# Stm32Printer.net
KiCad netlist of a schematic drawn in EasyEDA Pro
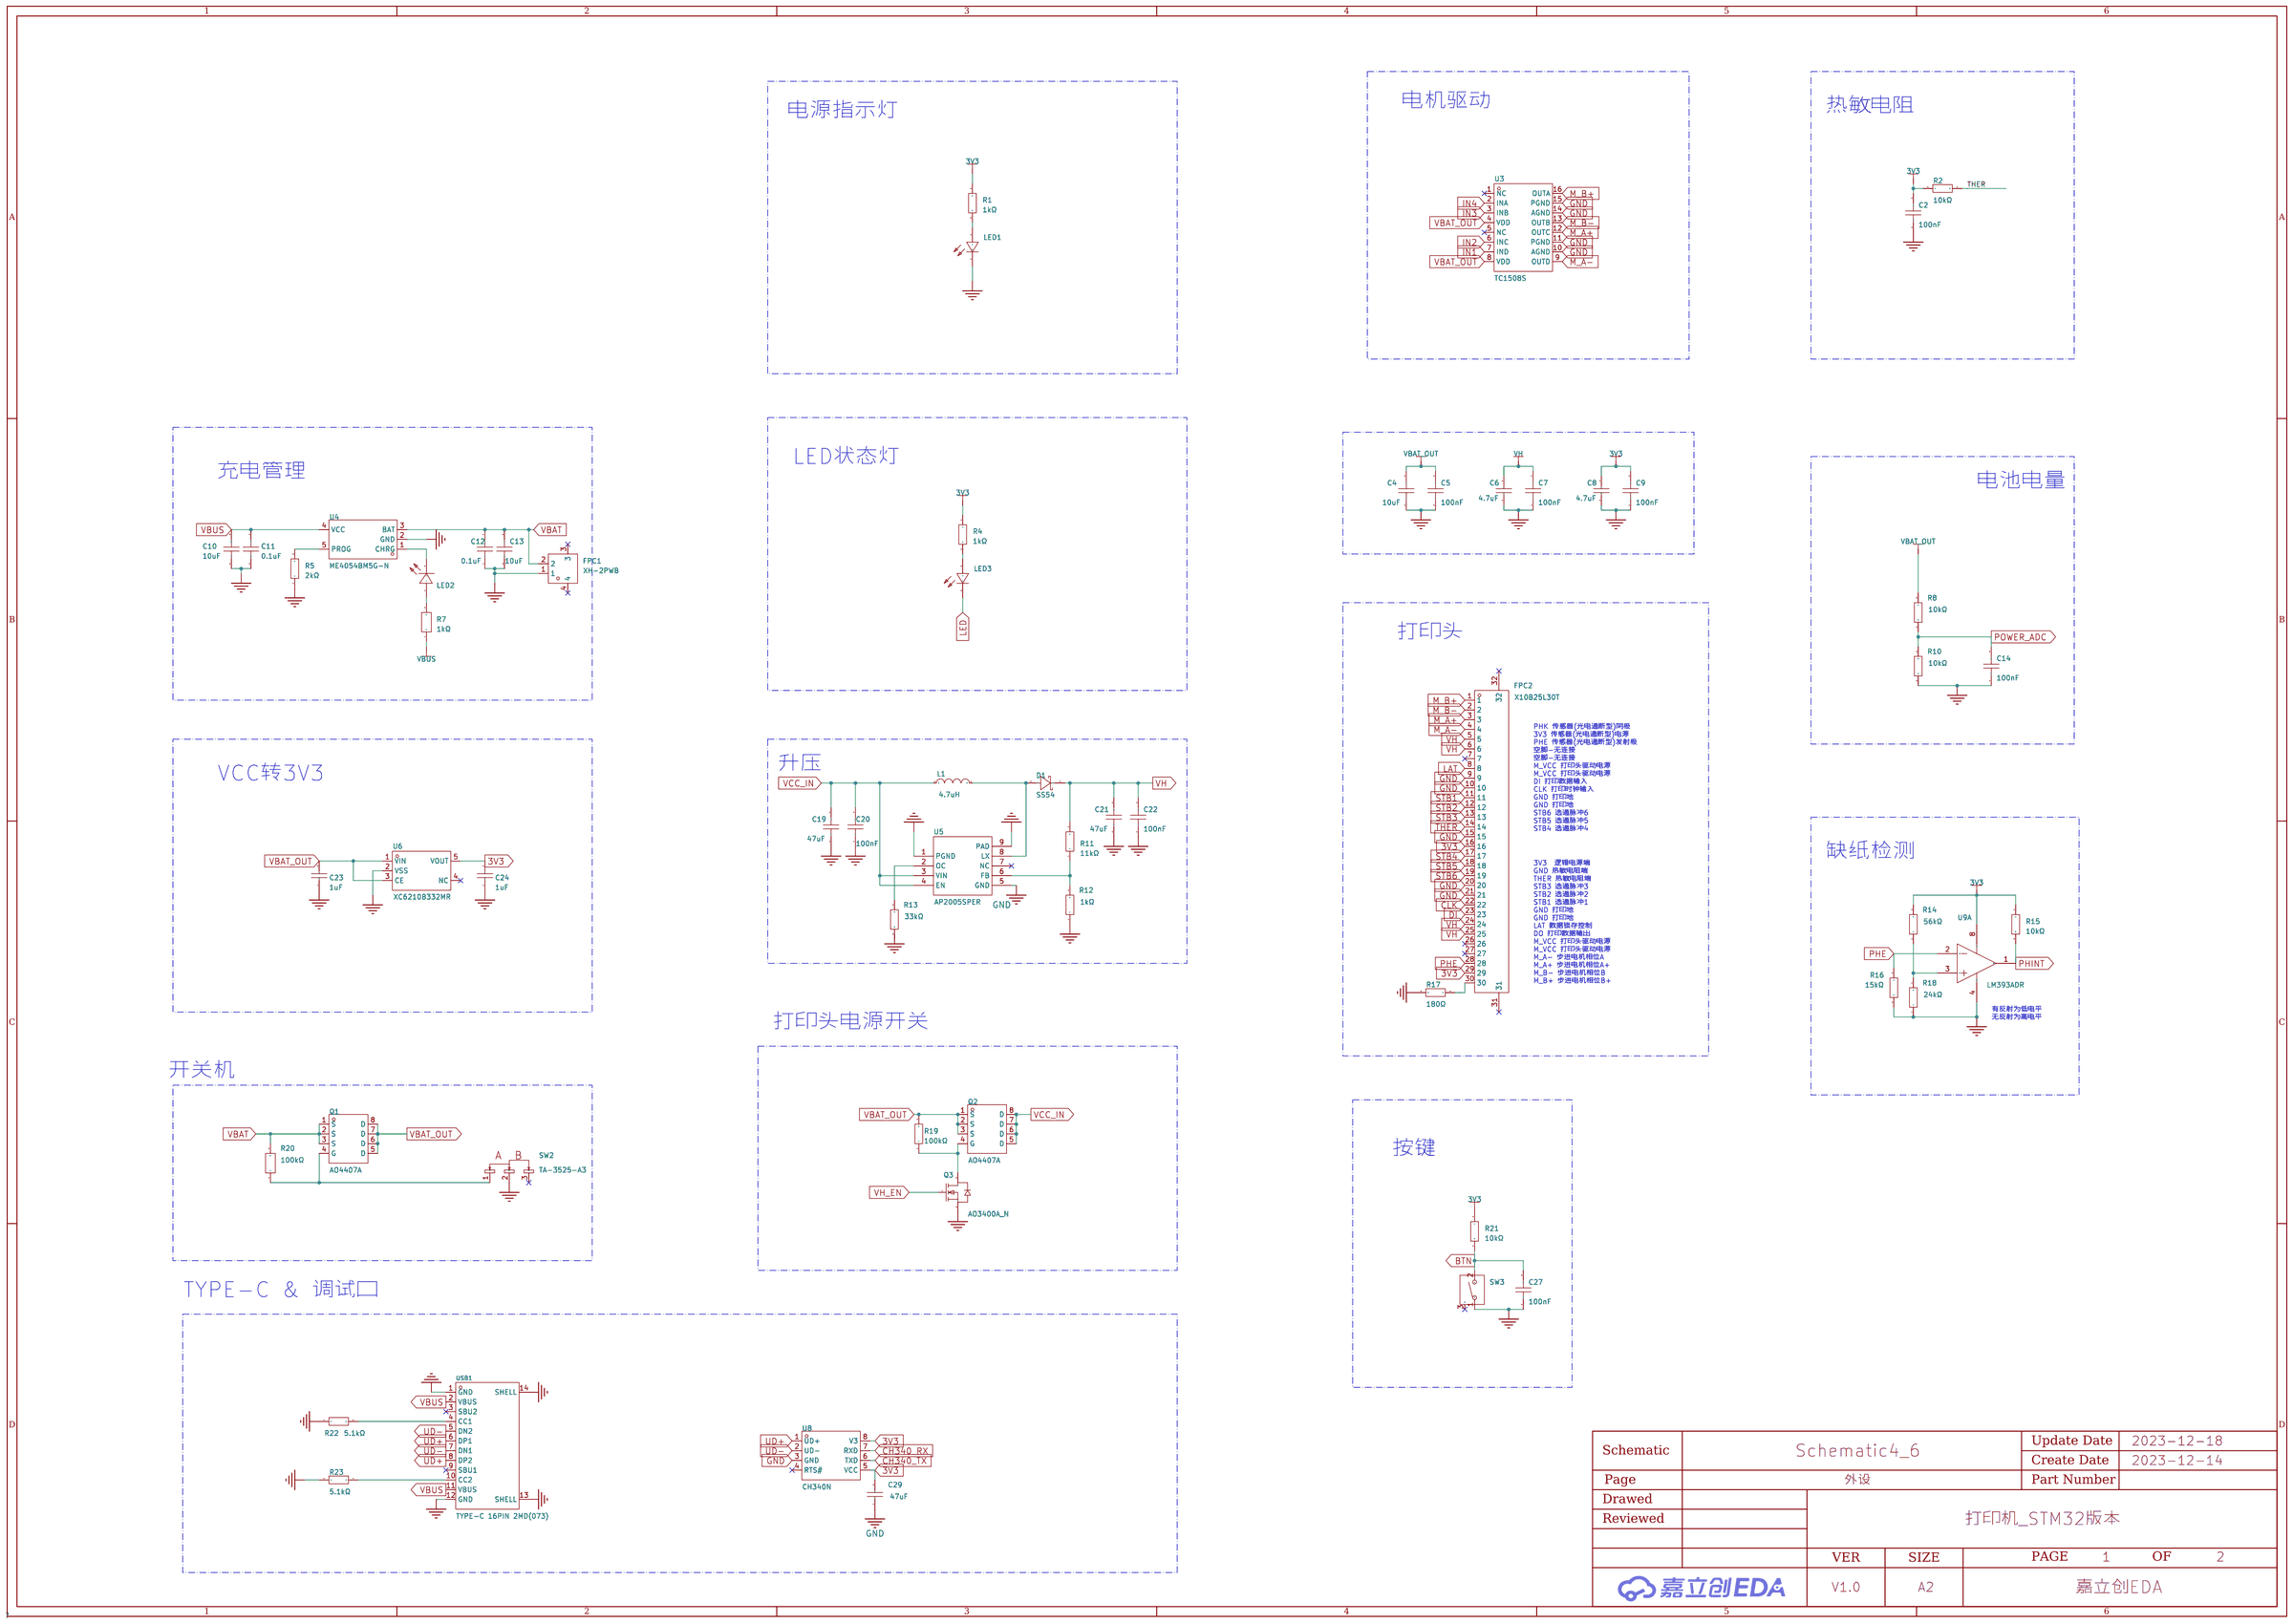
[diagram p0: 外设]
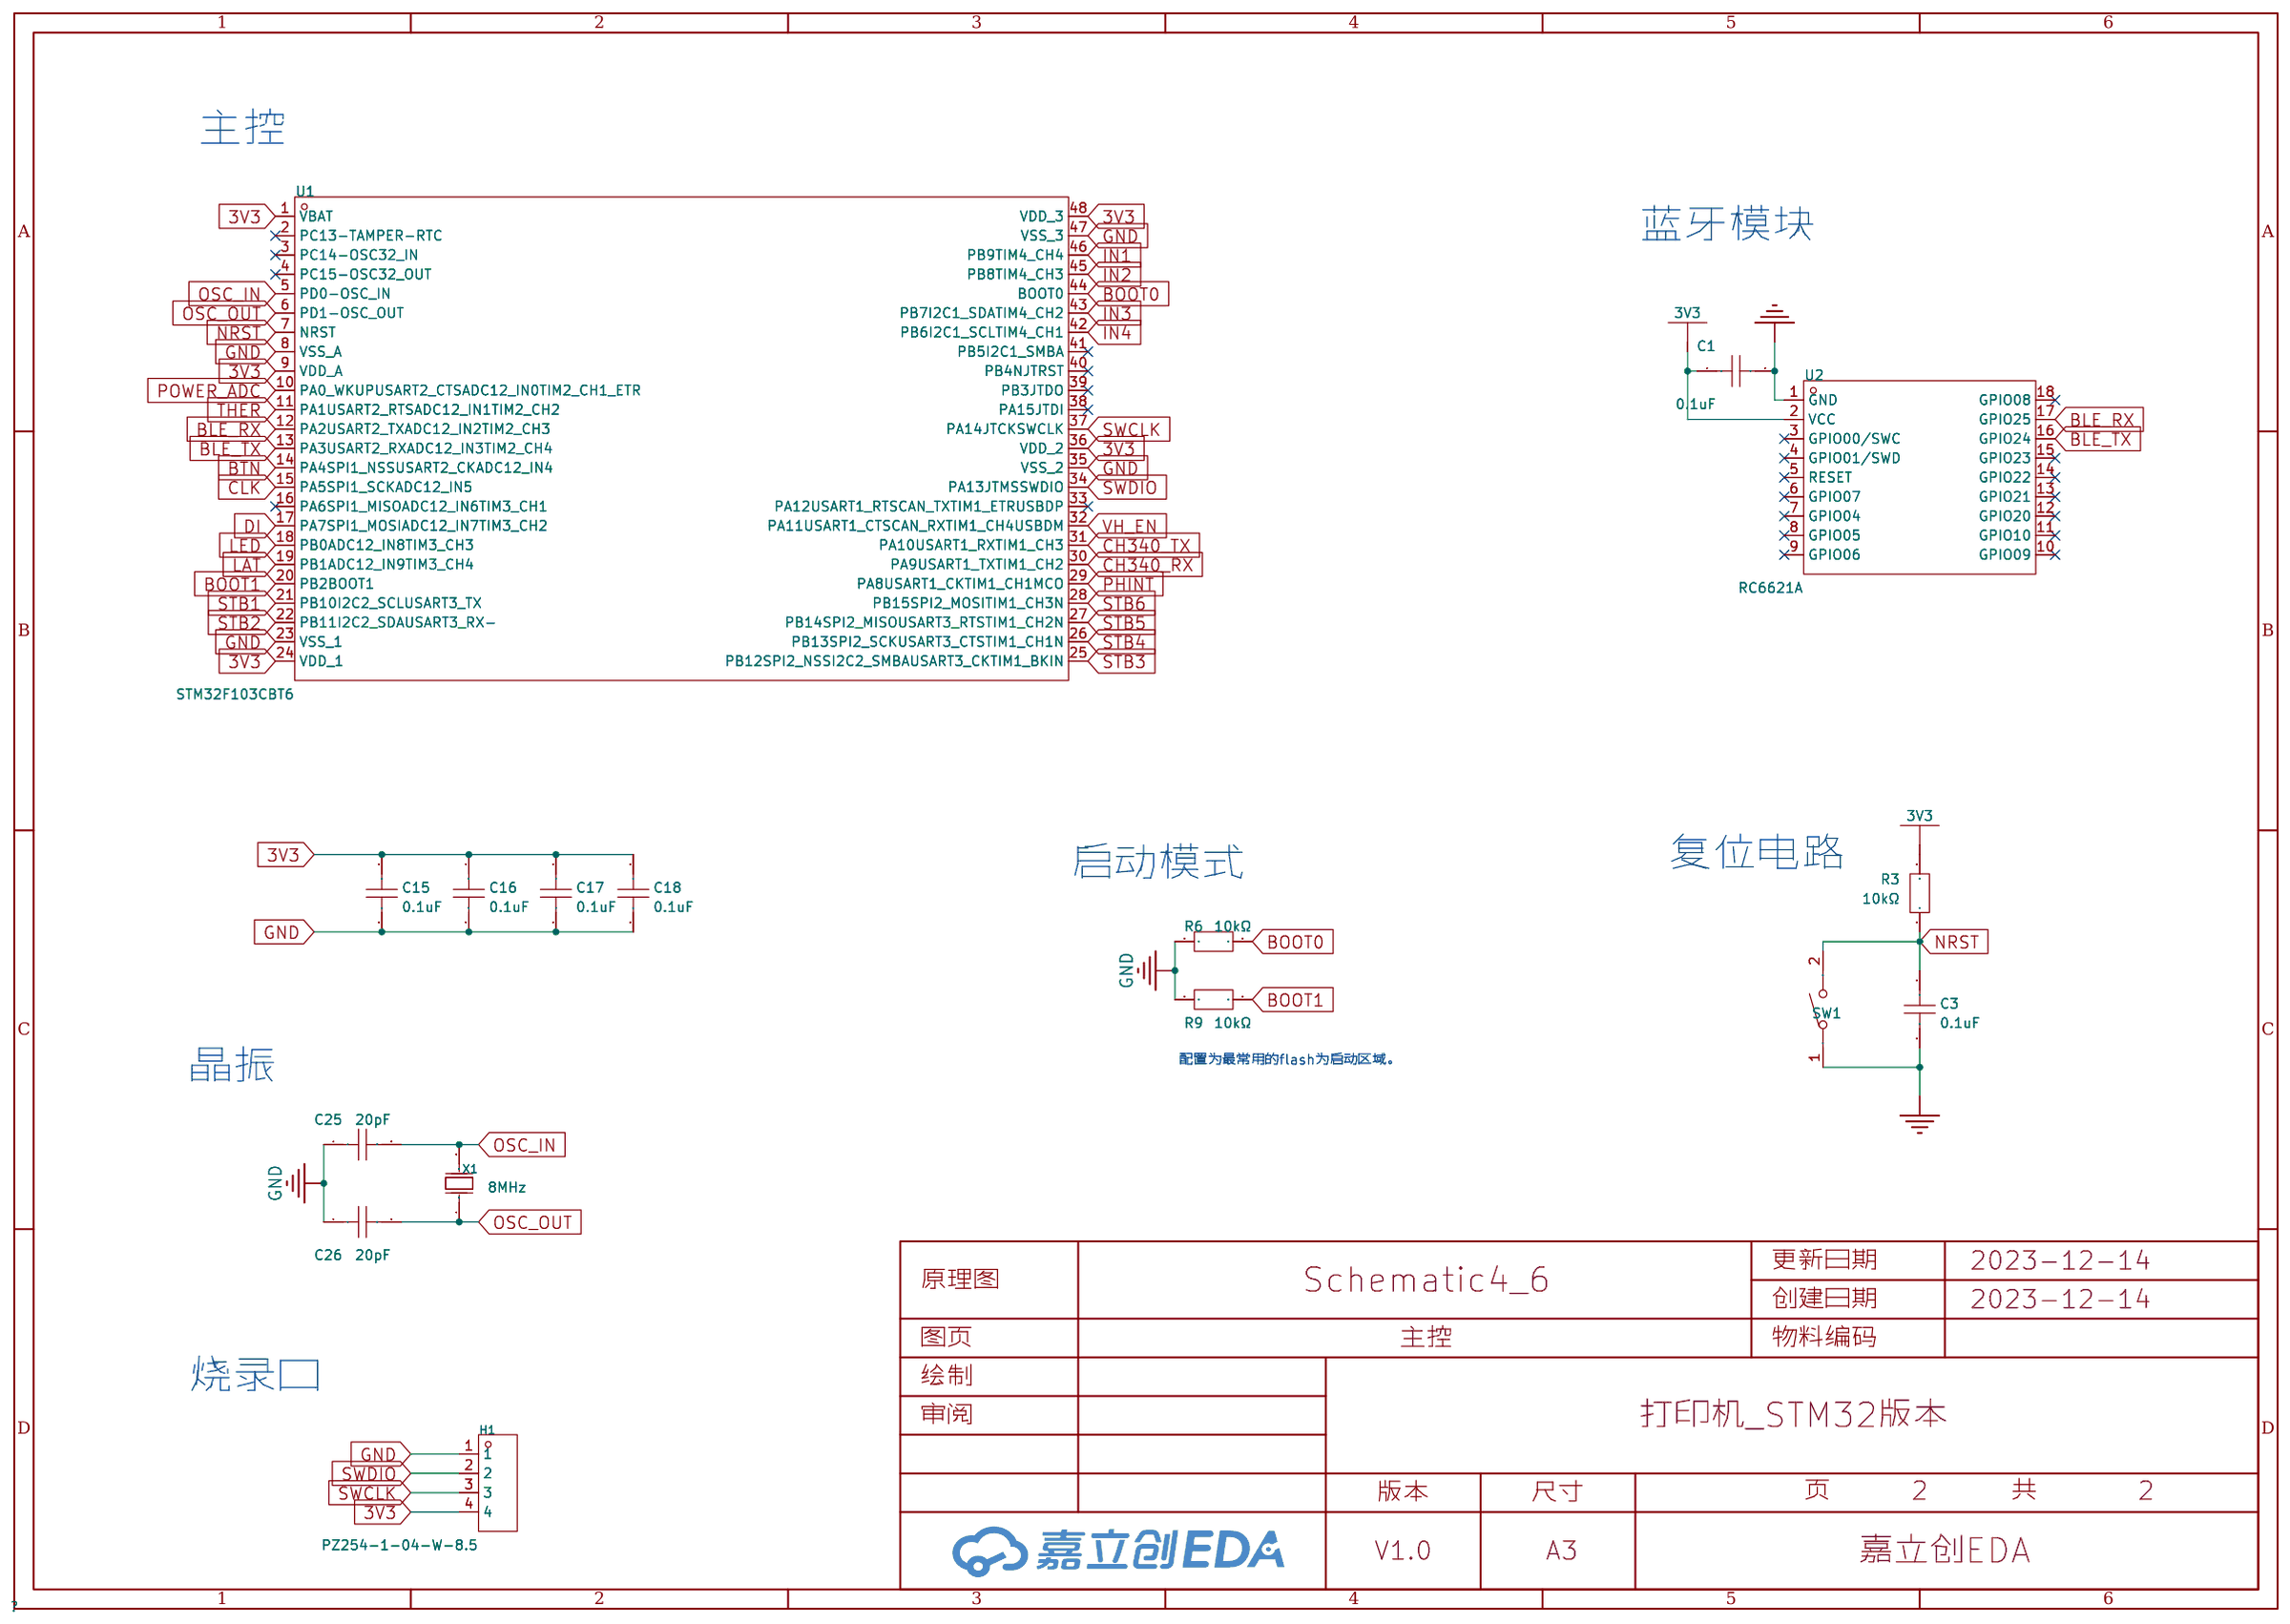
[diagram p1: 主控]

(export (version "E")
  (design (tool "Eeschema 10.0.6"))
  (components
    (comp (ref "C2")
      (value "100nF")
      (footprint "easyedapro:C0603")
      (description "容值:100nF;精度:±10%;额定电压:50V;材质(温度系数):X7R;")
      (fields
        (field (name "Manufacturer Part") "CL10B104KB8NNNC")
        (field (name "Manufacturer") "SAMSUNG(三星)")
      )
      (libsource (lib "easyedapro") (part "CL10B104KB8NNNC"))
    )
    (comp (ref "C4")
      (value "10uF")
      (footprint "easyedapro:C0603")
      (description "容值:10uF;精度:±20%;额定电压:25V;材质(温度系数):X5R;")
      (fields
        (field (name "Manufacturer Part") "CL10A106MA8NRNC")
        (field (name "Manufacturer") "SAMSUNG(三星)")
      )
      (libsource (lib "easyedapro") (part "CL10A106MA8NRNC"))
    )
    (comp (ref "C5")
      (value "100nF")
      (footprint "easyedapro:C0603")
      (description "容值:100nF;精度:±10%;额定电压:50V;材质(温度系数):X7R;")
      (fields
        (field (name "Manufacturer Part") "CL10B104KB8NNNC")
        (field (name "Manufacturer") "SAMSUNG(三星)")
      )
      (libsource (lib "easyedapro") (part "CL10B104KB8NNNC"))
    )
    (comp (ref "C6")
      (value "4.7uF")
      (footprint "easyedapro:C0603")
      (description "容值:4.7uF;精度:±10%;额定电压:25V;材质(温度系数):X5R;")
      (fields
        (field (name "Manufacturer Part") "CL10A475KA8NQNC")
        (field (name "Manufacturer") "SAMSUNG(三星)")
      )
      (libsource (lib "easyedapro") (part "CL10A475KA8NQNC"))
    )
    (comp (ref "C7")
      (value "100nF")
      (footprint "easyedapro:C0603")
      (description "容值:100nF;精度:±10%;额定电压:50V;材质(温度系数):X7R;")
      (fields
        (field (name "Manufacturer Part") "CL10B104KB8NNNC")
        (field (name "Manufacturer") "SAMSUNG(三星)")
      )
      (libsource (lib "easyedapro") (part "CL10B104KB8NNNC"))
    )
    (comp (ref "C8")
      (value "4.7uF")
      (footprint "easyedapro:C0603")
      (description "容值:4.7uF;精度:±10%;额定电压:25V;材质(温度系数):X5R;")
      (fields
        (field (name "Manufacturer Part") "CL10A475KA8NQNC")
        (field (name "Manufacturer") "SAMSUNG(三星)")
      )
      (libsource (lib "easyedapro") (part "CL10A475KA8NQNC"))
    )
    (comp (ref "C9")
      (value "100nF")
      (footprint "easyedapro:C0603")
      (description "容值:100nF;精度:±10%;额定电压:50V;材质(温度系数):X7R;")
      (fields
        (field (name "Manufacturer Part") "CL10B104KB8NNNC")
        (field (name "Manufacturer") "SAMSUNG(三星)")
      )
      (libsource (lib "easyedapro") (part "CL10B104KB8NNNC"))
    )
    (comp (ref "C10")
      (value "10uF")
      (fields
        (field (name "Manufacturer Part") "CL10A106MA8NRNC")
        (field (name "Manufacturer") "SAMSUNG(三星)")
      )
      (libsource (lib "easyedapro") (part "CL10A106MA8NRNC"))
    )
    (comp (ref "C11")
      (value "0.1uF")
      (footprint "easyedapro:c0603")
      (description "容值：100nF 精度：±10% 额定电压：50V 材质(温度系数)：X7R 材质:X7R")
      (fields (field (name "Manufacturer Part") "MT18N1R5C500CT") (field (name "Manufacturer") "华新科(Walsin)"))
      (libsource (lib "easyedapro") (part "mt18n1r5c500ct"))
    )
    (comp (ref "C12")
      (value "0.1uF")
      (footprint "easyedapro:c0603")
      (description "容值：100nF 精度：±10% 额定电压：50V 材质(温度系数)：X7R 材质:X7R")
      (fields (field (name "Manufacturer Part") "MT18N1R5C500CT") (field (name "Manufacturer") "华新科(Walsin)"))
      (libsource (lib "easyedapro") (part "mt18n1r5c500ct"))
    )
    (comp (ref "C13")
      (value "10uF")
      (fields
        (field (name "Manufacturer Part") "CL10A106MA8NRNC")
        (field (name "Manufacturer") "SAMSUNG(三星)")
      )
      (libsource (lib "easyedapro") (part "CL10A106MA8NRNC"))
    )
    (comp (ref "C14")
      (value "100nF")
      (footprint "easyedapro:C0603")
      (description "容值:100nF;精度:±10%;额定电压:50V;材质(温度系数):X7R;")
      (fields
        (field (name "Manufacturer Part") "CL10B104KB8NNNC")
        (field (name "Manufacturer") "SAMSUNG(三星)")
      )
      (libsource (lib "easyedapro") (part "CL10B104KB8NNNC"))
    )
    (comp (ref "C19")
      (value "47uF")
      (footprint "easyedapro:C1206")
      (description "容值:47uF;精度:±20%;额定电压:10V;材质(温度系数):X5R;")
      (fields
        (field (name "Manufacturer Part") "CL31A476MPHNNNE")
        (field (name "Manufacturer") "SAMSUNG(三星)")
      )
      (libsource (lib "easyedapro") (part "CL31A476MPHNNNE"))
    )
    (comp (ref "C20")
      (value "100nF")
      (footprint "easyedapro:C0603")
      (description "容值:100nF;精度:±10%;额定电压:50V;材质(温度系数):X7R;")
      (fields
        (field (name "Manufacturer Part") "CL10B104KB8NNNC")
        (field (name "Manufacturer") "SAMSUNG(三星)")
      )
      (libsource (lib "easyedapro") (part "CL10B104KB8NNNC"))
    )
    (comp (ref "C21")
      (value "47uF")
      (footprint "easyedapro:C1206")
      (description "容值:47uF;精度:±20%;额定电压:10V;材质(温度系数):X5R;")
      (fields
        (field (name "Manufacturer Part") "CL31A476MPHNNNE")
        (field (name "Manufacturer") "SAMSUNG(三星)")
      )
      (libsource (lib "easyedapro") (part "CL31A476MPHNNNE"))
    )
    (comp (ref "C22")
      (value "100nF")
      (footprint "easyedapro:C0603")
      (description "容值:100nF;精度:±10%;额定电压:50V;材质(温度系数):X7R;")
      (fields
        (field (name "Manufacturer Part") "CL10B104KB8NNNC")
        (field (name "Manufacturer") "SAMSUNG(三星)")
      )
      (libsource (lib "easyedapro") (part "CL10B104KB8NNNC"))
    )
    (comp (ref "C23")
      (value "1uF")
      (footprint "easyedapro:C0603")
      (description "容值:1uF;精度:±10%;额定电压:50V;材质(温度系数):X5R;")
      (fields
        (field (name "Manufacturer Part") "CL10A105KB8NNNC")
        (field (name "Manufacturer") "SAMSUNG(三星)")
      )
      (libsource (lib "easyedapro") (part "CL10A105KB8NNNC"))
    )
    (comp (ref "C24")
      (value "1uF")
      (footprint "easyedapro:C0603")
      (description "容值:1uF;精度:±10%;额定电压:50V;材质(温度系数):X5R;")
      (fields
        (field (name "Manufacturer Part") "CL10A105KB8NNNC")
        (field (name "Manufacturer") "SAMSUNG(三星)")
      )
      (libsource (lib "easyedapro") (part "CL10A105KB8NNNC"))
    )
    (comp (ref "C27")
      (value "100nF")
      (footprint "easyedapro:C0603")
      (description "容值:100nF;精度:±10%;额定电压:50V;材质(温度系数):X7R;")
      (fields
        (field (name "Manufacturer Part") "CL10B104KB8NNNC")
        (field (name "Manufacturer") "SAMSUNG(三星)")
      )
      (libsource (lib "easyedapro") (part "CL10B104KB8NNNC"))
    )
    (comp (ref "C29")
      (value "47uF")
      (footprint "easyedapro:C0603")
      (description "容值:47uF;精度:±20%;额定电压:6.3V;材质(温度系数):X5R;")
      (fields
        (field (name "Manufacturer Part") "GRM188R60J476ME15D")
        (field (name "Manufacturer") "muRata(村田)")
      )
      (libsource (lib "easyedapro") (part "GRM188R60J476ME15D"))
    )
    (comp (ref "D1")
      (value "SS54")
      (footprint "easyedapro:SMA_L4.3-W2.6-LS5.0-RD")
      (description "二极管配置:独立式;直流反向耐压(Vr):40V;平均整流电流(Io):5A;正向压降(Vf):550mV@5A;反向电流(Ir):500uA@40V;")
      (fields (field (name "Manufacturer") "TWGMC(台湾迪嘉)"))
      (libsource (lib "easyedapro") (part "SS54_C727065"))
    )
    (comp (ref "FPC1")
      (value "XH-2PWB")
      (footprint "easyedapro:CONN-SMD_2P-P2.50_DEALON_XH-2PWB_C2905024")
      (description "参考系列:XH;间距:2.5mm;插针结构:1x2P;排数:1;每排PIN数:2;行距:-;公母:公型插针;安装方式:卧贴;额定电流:3A;工作温度范围:-25~+85;")
      (fields (field (name "Manufacturer") "DEALON(德艺隆)"))
      (libsource (lib "easyedapro") (part "XH-2PWB_C2905024"))
    )
    (comp (ref "FPC2")
      (value "X10B25L30T")
      (footprint "easyedapro:FPC-SMD_X10B25U30T")
      (description "间距:1mm;触点数量:30;锁定特性:抽屉式;安装类型:卧贴;触点类型:下接;工作温度范围:-40~+85;焊接温度(最大值):260;")
      (fields (field (name "Manufacturer") "XKB Connectivity(中国星坤)"))
      (libsource (lib "easyedapro") (part "X10B25L30T"))
    )
    (comp (ref "L1")
      (value "4.7uH")
      (footprint "easyedapro:IND-SMD_L6.0-W6.0")
      (description "电感值:4.7uH;精度:±20%;额定电流:4A;直流电阻(DCR):27.6mΩ;")
      (fields (field (name "Manufacturer Part") "1255AY-4R7M=P3") (field (name "Manufacturer") "muRata(村田)"))
      (libsource (lib "easyedapro") (part "1255AY-4R7M=P3"))
    )
    (comp (ref "LED1")
      (value "NCD0603R1")
      (footprint "easyedapro:LED0603-RD_RED")
      (description "发光颜色:红灯;")
      (fields (field (name "Manufacturer") "国星光电"))
      (libsource (lib "easyedapro") (part "FC-DA1608HRK-620D"))
    )
    (comp (ref "LED2")
      (value "TLMG1100-GS08")
      (footprint "easyedapro:LED0603-R-RD_GREEN")
      (description "照明颜色:普绿/黄绿;色温 - CCT（K）:-;主波长/色坐标:570nm;")
      (fields (field (name "Manufacturer") "VISHAY(威世)"))
      (libsource (lib "easyedapro") (part "TLMG1100-GS08"))
    )
    (comp (ref "LED3")
      (value "NCD0603R1")
      (footprint "easyedapro:LED0603-RD_RED")
      (description "发光颜色:红灯;")
      (fields (field (name "Manufacturer") "国星光电"))
      (libsource (lib "easyedapro") (part "FC-DA1608HRK-620D"))
    )
    (comp (ref "Q1")
      (value "AO4407A")
      (footprint "easyedapro:SOP-8_L5.0-W4.0-P1.27-LS6.0-BL")
      (fields (field (name "Manufacturer") "UMW(友台半导体)"))
      (libsource (lib "easyedapro") (part "AO4407A_C2841482"))
    )
    (comp (ref "Q2")
      (value "AO4407A")
      (footprint "easyedapro:SOP-8_L5.0-W4.0-P1.27-LS6.0-BL")
      (fields (field (name "Manufacturer") "UMW(友台半导体)"))
      (libsource (lib "easyedapro") (part "AO4407A_C2841482"))
    )
    (comp (ref "Q3")
      (value "AO3400A_N")
      (footprint "easyedapro:SOT-23-3_L2.9-W1.3-P1.90-LS2.4-BR")
      (fields (field (name "Manufacturer Part") "AO3400A") (field (name "Manufacturer") "UMW(友台半导体)"))
      (libsource (lib "easyedapro") (part "AO3400A_C347475"))
    )
    (comp (ref "R1")
      (value "1kΩ")
      (footprint "easyedapro:R0603")
      (description "阻值:1kΩ;精度:±1%;功率:100mW;")
      (fields (field (name "Manufacturer Part") "RMC06031K1%N") (field (name "Manufacturer") "Tyohm(幸亚电阻)"))
      (libsource (lib "easyedapro") (part "RMC06031K1%N"))
    )
    (comp (ref "R2")
      (value "10kΩ")
      (footprint "easyedapro:R0603")
      (description "电阻类型:厚膜电阻;阻值:10kΩ;精度:±1%;功率:100mW;温度系数:±100ppm/;最大工作电压:75V;工作温度范围:-55~+155;")
      (fields
        (field (name "Manufacturer Part") "0603WAF1002T5E")
        (field (name "Manufacturer") "UNI-ROYAL(厚声)")
      )
      (libsource (lib "easyedapro") (part "0603WAF1002T5E"))
    )
    (comp (ref "R4")
      (value "1kΩ")
      (footprint "easyedapro:R0603")
      (description "阻值:1kΩ;精度:±1%;功率:100mW;")
      (fields (field (name "Manufacturer Part") "RMC06031K1%N") (field (name "Manufacturer") "Tyohm(幸亚电阻)"))
      (libsource (lib "easyedapro") (part "RMC06031K1%N"))
    )
    (comp (ref "R5")
      (value "2kΩ")
      (description "精度:±1%;阻值:2kΩ;温度系数:±100ppm/;功率:1/10W;最大工作电压:75V;工作温度范围:-55~+155;")
      (fields
        (field (name "Manufacturer Part") "0603WAF2001T5E")
        (field (name "Manufacturer") "UNI-ROYAL(厚声)")
      )
      (libsource (lib "easyedapro") (part "0603WAF2001T5E"))
    )
    (comp (ref "R7")
      (value "1kΩ")
      (footprint "easyedapro:R0603")
      (fields (field (name "Manufacturer Part") "ERA3VEB1001V") (field (name "Manufacturer") "PANASONIC(松下)"))
      (libsource (lib "easyedapro") (part "ERA3VEB1001V"))
    )
    (comp (ref "R8")
      (value "10kΩ")
      (footprint "easyedapro:R0603")
      (description "电阻类型:厚膜电阻;阻值:10kΩ;精度:±1%;功率:100mW;温度系数:±100ppm/;最大工作电压:75V;工作温度范围:-55~+155;")
      (fields
        (field (name "Manufacturer Part") "0603WAF1002T5E")
        (field (name "Manufacturer") "UNI-ROYAL(厚声)")
      )
      (libsource (lib "easyedapro") (part "0603WAF1002T5E"))
    )
    (comp (ref "R10")
      (value "10kΩ")
      (footprint "easyedapro:R0603")
      (description "电阻类型:厚膜电阻;阻值:10kΩ;精度:±1%;功率:100mW;温度系数:±100ppm/;最大工作电压:75V;工作温度范围:-55~+155;")
      (fields
        (field (name "Manufacturer Part") "0603WAF1002T5E")
        (field (name "Manufacturer") "UNI-ROYAL(厚声)")
      )
      (libsource (lib "easyedapro") (part "0603WAF1002T5E"))
    )
    (comp (ref "R11")
      (value "11kΩ")
      (footprint "easyedapro:R0603")
      (description "电阻类型:厚膜电阻;阻值:11kΩ;精度:±5%;功率:100mW;温度系数:±100ppm/;最大工作电压:75V;工作温度范围:-55~+155;")
      (fields
        (field (name "Manufacturer Part") "0603WAJ0113T5E")
        (field (name "Manufacturer") "UNI-ROYAL(厚声)")
      )
      (libsource (lib "easyedapro") (part "0603WAJ0113T5E"))
    )
    (comp (ref "R12")
      (value "1kΩ")
      (footprint "easyedapro:R0603")
      (description "阻值:1kΩ;精度:±1%;功率:100mW;")
      (fields (field (name "Manufacturer Part") "RMC06031K1%N") (field (name "Manufacturer") "Tyohm(幸亚电阻)"))
      (libsource (lib "easyedapro") (part "RMC06031K1%N"))
    )
    (comp (ref "R13")
      (value "33kΩ")
      (footprint "easyedapro:R0603")
      (description "电阻类型:厚膜电阻;阻值:33kΩ;精度:±1%;功率:100mW;温度系数:±100ppm/;最大工作电压:75V;工作温度范围:-55~+155;")
      (fields
        (field (name "Manufacturer Part") "0603WAF3302T5E")
        (field (name "Manufacturer") "UNI-ROYAL(厚声)")
      )
      (libsource (lib "easyedapro") (part "0603WAF3302T5E"))
    )
    (comp (ref "R14")
      (value "56kΩ")
      (footprint "easyedapro:R0603")
      (description "电阻类型:厚膜电阻;阻值:56kΩ;精度:±1%;功率:100mW;温度系数:±100ppm/;最大工作电压:75V;工作温度范围:-55~+155;")
      (fields
        (field (name "Manufacturer Part") "0603WAF5602T5E")
        (field (name "Manufacturer") "UNI-ROYAL(厚声)")
      )
      (libsource (lib "easyedapro") (part "0603WAF5602T5E"))
    )
    (comp (ref "R15")
      (value "10kΩ")
      (footprint "easyedapro:R0603")
      (description "电阻类型:厚膜电阻;阻值:10kΩ;精度:±1%;功率:100mW;温度系数:±100ppm/;最大工作电压:75V;工作温度范围:-55~+155;")
      (fields
        (field (name "Manufacturer Part") "0603WAF1002T5E")
        (field (name "Manufacturer") "UNI-ROYAL(厚声)")
      )
      (libsource (lib "easyedapro") (part "0603WAF1002T5E"))
    )
    (comp (ref "R16")
      (value "15kΩ")
      (footprint "easyedapro:R0603")
      (description "电阻类型:厚膜电阻;阻值:15kΩ;精度:±1%;功率:100mW;温度系数:±100ppm/;最大工作电压:75V;工作温度范围:-55~+155;")
      (fields
        (field (name "Manufacturer Part") "0603WAF1502T5E")
        (field (name "Manufacturer") "UNI-ROYAL(厚声)")
      )
      (libsource (lib "easyedapro") (part "0603WAF1502T5E"))
    )
    (comp (ref "R17")
      (value "180Ω")
      (footprint "easyedapro:R0603")
      (description "电阻类型:厚膜电阻;阻值:180Ω;精度:±1%;功率:100mW;温度系数:±100ppm/;最大工作电压:75V;工作温度范围:-55~+155;")
      (fields
        (field (name "Manufacturer Part") "0603WAF1800T5E")
        (field (name "Manufacturer") "UNI-ROYAL(厚声)")
      )
      (libsource (lib "easyedapro") (part "0603WAF1800T5E"))
    )
    (comp (ref "R18")
      (value "24kΩ")
      (footprint "easyedapro:R0603")
      (description "电阻类型:厚膜电阻;阻值:24kΩ;精度:±1%;功率:100mW;温度系数:±100ppm/;最大工作电压:75V;工作温度范围:-55~+155;")
      (fields
        (field (name "Manufacturer Part") "0603WAF2402T5E")
        (field (name "Manufacturer") "UNI-ROYAL(厚声)")
      )
      (libsource (lib "easyedapro") (part "0603WAF2402T5E"))
    )
    (comp (ref "R19")
      (value "100kΩ")
      (footprint "easyedapro:R0603")
      (description "电阻类型:厚膜电阻;阻值:100kΩ;精度:±1%;功率:100mW;温度系数:±100ppm/;最大工作电压:75V;工作温度范围:-55~+155;")
      (fields
        (field (name "Manufacturer Part") "0603WAF1003T5E")
        (field (name "Manufacturer") "UNI-ROYAL(厚声)")
      )
      (libsource (lib "easyedapro") (part "0603WAF1003T5E"))
    )
    (comp (ref "R20")
      (value "100kΩ")
      (footprint "easyedapro:R0603")
      (fields (field (name "Manufacturer Part") "ERA3VEB1003V") (field (name "Manufacturer") "PANASONIC(松下)"))
      (libsource (lib "easyedapro") (part "ERA3VEB1003V"))
    )
    (comp (ref "R21")
      (value "10kΩ")
      (footprint "easyedapro:R0603")
      (description "阻值:10kΩ;精度:±1%;功率:100mW;温度系数:±100ppm/;最大工作电压:-;工作温度范围:-55~+155;")
      (fields (field (name "Manufacturer Part") "ERJ3EKF1002V") (field (name "Manufacturer") "PANASONIC(松下)"))
      (libsource (lib "easyedapro") (part "ERJ-3EKF1002V"))
    )
    (comp (ref "R22")
      (value "5.1kΩ")
      (footprint "easyedapro:R0603")
      (description "电阻类型:厚膜电阻;阻值:5.1kΩ;精度:±1%;功率:100mW;温度系数:±100ppm/;最大工作电压:75V;工作温度范围:-55~+155;")
      (fields
        (field (name "Manufacturer Part") "0603WAF5101T5E")
        (field (name "Manufacturer") "UNI-ROYAL(厚声)")
      )
      (libsource (lib "easyedapro") (part "0603WAF5101T5E"))
    )
    (comp (ref "R23")
      (value "5.1kΩ")
      (footprint "easyedapro:R0603")
      (description "电阻类型:厚膜电阻;阻值:5.1kΩ;精度:±1%;功率:100mW;温度系数:±100ppm/;最大工作电压:75V;工作温度范围:-55~+155;")
      (fields
        (field (name "Manufacturer Part") "0603WAF5101T5E")
        (field (name "Manufacturer") "UNI-ROYAL(厚声)")
      )
      (libsource (lib "easyedapro") (part "0603WAF5101T5E"))
    )
    (comp (ref "SW2")
      (value "TA-3525-A3")
      (footprint "easyedapro:SW-SMD_3P-L9.1-W3.5-P2.50-EH6.8")
      (fields (field (name "Manufacturer") "Yuandi(元迪)"))
      (libsource (lib "easyedapro") (part "TA-3525-A3"))
    )
    (comp (ref "SW3")
      (value "TS4538B3JTP 250gf 121")
      (footprint "easyedapro:KEY-SMD_3P-L4.5-W3.8-P3.00-LS4.5-BL")
      (fields (field (name "Manufacturer") "SHOU HAN(首韩)"))
      (libsource (lib "easyedapro") (part "TS4538B3JTP 250GF 121"))
    )
    (comp (ref "U3")
      (value "TC1508S")
      (footprint "easyedapro:SOP-16_L10.0-W3.9-P1.27-LS6.0-BL")
      (description "双通道直流马达驱动器")
      (fields (field (name "Manufacturer") "FM富满"))
      (libsource (lib "easyedapro") (part "TC1508S"))
    )
    (comp (ref "U4")
      (value "ME4054BM5G-N")
      (footprint "easyedapro:TSOT-23-5_L2.9-W1.6-P0.95-LS2.8-BL")
      (fields (field (name "Manufacturer") "MICRONE(南京微盟)"))
      (libsource (lib "easyedapro") (part "ME4054BM5G-N"))
    )
    (comp (ref "U5")
      (value "AP2005SPER")
      (footprint "easyedapro:ESOP-8_L4.9-W3.9-P1.27-LS6.0-BL-EP")
      (description "功能类型:升压型;同步整流:否;输出通道数:1;拓扑结构:升压式;输入电压:2.5V~5.5V;输出电压:9V;输出电流(最大值):-;开关频率:1MHz;")
      (fields (field (name "Manufacturer") "chipown(芯朋微电子)"))
      (libsource (lib "easyedapro") (part "AP2005SPER"))
    )
    (comp (ref "U6")
      (value "XC6210B332MR")
      (footprint "easyedapro:TSOT-23-5_L2.9-W1.6-P0.95-LS2.8-BR")
      (description "输出类型:固定;输出极性:正;输出通道数:1;最大输入电压:6V;输出电压:3.3V;压差:75mV@(100mA);输出电流:900mA;电源纹波抑制比(PSRR):60dB@(1kHz);")
      (fields (field (name "Manufacturer") "TOREX(特瑞仕)"))
      (libsource (lib "easyedapro") (part "XC6210B332MR_C424705"))
    )
    (comp (ref "U8")
      (value "CH340N")
      (footprint "easyedapro:SOP-8_L4.9-W3.9-P1.27-LS6.0-BL")
      (fields (field (name "Manufacturer") "WCH(南京沁恒)"))
      (libsource (lib "easyedapro") (part "CH340N_C2977777"))
    )
    (comp (ref "U9")
      (value "LM393ADR")
      (footprint "easyedapro:SOP-8_L4.9-W3.9-P1.27-LS6.0-BL")
      (description "比较器组数:-;电源电压:-;各通道供电电流:-;输出类型:-;传播延迟:-;")
      (fields (field (name "Manufacturer") "UMW(友台半导体)"))
      (libsource (lib "easyedapro") (part "LM393ADR_C404321"))
    )
    (comp (ref "USB1")
      (value "TYPE-C 16PIN 2MD(073)")
      (footprint "easyedapro:USB-C-SMD_TYPE-C-6PIN-2MD-073")
      (description "连接器类型:Type-C;标准:-;公母:母座;触点数量:16;端口数量:1;安装方式:卧贴;额定电流 - 电源:5A;工作温度范围:-25~+85;")
      (fields (field (name "Manufacturer") "SHOU HAN(首韩)"))
      (libsource (lib "easyedapro") (part "TYPE-C 16PIN 2MD(073)"))
    )
    (comp (ref "C1")
      (value "0.1uF")
      (footprint "easyedapro:c0603")
      (description "容值：100nF 精度：±10% 额定电压：50V 材质(温度系数)：X7R 材质:X7R")
      (fields (field (name "Manufacturer Part") "MT18N1R5C500CT") (field (name "Manufacturer") "华新科(Walsin)"))
      (libsource (lib "easyedapro") (part "mt18n1r5c500ct"))
    )
    (comp (ref "C3")
      (value "0.1uF")
      (footprint "easyedapro:c0603")
      (description "容值：100nF 精度：±10% 额定电压：50V 材质(温度系数)：X7R 材质:X7R")
      (fields (field (name "Manufacturer Part") "MT18N1R5C500CT") (field (name "Manufacturer") "华新科(Walsin)"))
      (libsource (lib "easyedapro") (part "mt18n1r5c500ct"))
    )
    (comp (ref "C15")
      (value "0.1uF")
      (footprint "easyedapro:c0603")
      (description "容值：100nF 精度：±10% 额定电压：50V 材质(温度系数)：X7R 材质:X7R")
      (fields (field (name "Manufacturer Part") "MT18N1R5C500CT") (field (name "Manufacturer") "华新科(Walsin)"))
      (libsource (lib "easyedapro") (part "mt18n1r5c500ct"))
    )
    (comp (ref "C16")
      (value "0.1uF")
      (footprint "easyedapro:c0603")
      (description "容值：100nF 精度：±10% 额定电压：50V 材质(温度系数)：X7R 材质:X7R")
      (fields (field (name "Manufacturer Part") "MT18N1R5C500CT") (field (name "Manufacturer") "华新科(Walsin)"))
      (libsource (lib "easyedapro") (part "mt18n1r5c500ct"))
    )
    (comp (ref "C17")
      (value "0.1uF")
      (footprint "easyedapro:c0603")
      (description "容值：100nF 精度：±10% 额定电压：50V 材质(温度系数)：X7R 材质:X7R")
      (fields (field (name "Manufacturer Part") "MT18N1R5C500CT") (field (name "Manufacturer") "华新科(Walsin)"))
      (libsource (lib "easyedapro") (part "mt18n1r5c500ct"))
    )
    (comp (ref "C18")
      (value "0.1uF")
      (footprint "easyedapro:c0603")
      (description "容值：100nF 精度：±10% 额定电压：50V 材质(温度系数)：X7R 材质:X7R")
      (fields (field (name "Manufacturer Part") "MT18N1R5C500CT") (field (name "Manufacturer") "华新科(Walsin)"))
      (libsource (lib "easyedapro") (part "mt18n1r5c500ct"))
    )
    (comp (ref "C25")
      (value "20pF")
      (footprint "easyedapro:C0603")
      (description "容值:20pF;精度:±1%;额定电压:50V;材质(温度系数):C0G;")
      (fields (field (name "Manufacturer Part") "0603CG200F500NT") (field (name "Manufacturer") "FH(风华)"))
      (libsource (lib "easyedapro") (part "0603CG200F500NT"))
    )
    (comp (ref "C26")
      (value "20pF")
      (footprint "easyedapro:C0603")
      (description "容值:20pF;精度:±1%;额定电压:50V;材质(温度系数):C0G;")
      (fields (field (name "Manufacturer Part") "0603CG200F500NT") (field (name "Manufacturer") "FH(风华)"))
      (libsource (lib "easyedapro") (part "0603CG200F500NT"))
    )
    (comp (ref "H1")
      (value "PZ254-1-04-W-8.5")
      (footprint "easyedapro:HDR-TH_04P-P2.54-H-M-W10.4-N")
      (fields (field (name "Manufacturer") "HCTL(华灿天禄)"))
      (libsource (lib "easyedapro") (part "PZ254-1-04-W-8.5"))
    )
    (comp (ref "R3")
      (value "10kΩ")
      (footprint "easyedapro:r0603")
      (description "阻值:10kΩ;精度:±1%;功率:-;温度系数:-;")
      (fields (field (name "Manufacturer Part") "SG73P1JTTD1002F") (field (name "Manufacturer") "KOA"))
      (libsource (lib "easyedapro") (part "sg73p1jttd1002f"))
    )
    (comp (ref "R6")
      (value "10kΩ")
      (footprint "easyedapro:r0603")
      (description "阻值:10kΩ;精度:±1%;功率:-;温度系数:-;")
      (fields (field (name "Manufacturer Part") "SG73P1JTTD1002F") (field (name "Manufacturer") "KOA"))
      (libsource (lib "easyedapro") (part "sg73p1jttd1002f"))
    )
    (comp (ref "R9")
      (value "10kΩ")
      (footprint "easyedapro:r0603")
      (description "阻值:10kΩ;精度:±1%;功率:-;温度系数:-;")
      (fields (field (name "Manufacturer Part") "SG73P1JTTD1002F") (field (name "Manufacturer") "KOA"))
      (libsource (lib "easyedapro") (part "sg73p1jttd1002f"))
    )
    (comp (ref "SW1")
      (value "TS-1088-AR02016")
      (footprint "easyedapro:SW-SMD_L3.9-W3.0-P4.45")
      (description "触点电流:50mA;额定电压(DC):12V;绝缘电阻:100MΩ;电路结构:单刀单掷;安装方式:立贴;作用力:160gf@±50gf;机械寿命:10万次;带支架:否;")
      (fields (field (name "Manufacturer") "XUNPU(讯普)"))
      (libsource (lib "easyedapro") (part "TS-1088-AR02016"))
    )
    (comp (ref "U1")
      (value "STM32F103CBT6")
      (footprint "easyedapro:LQFP-48_L7.0-W7.0-P0.50-LS9.0-BL")
      (description "CPU内核:ARM Cortex-M3;CPU最大主频:72MHz;程序存储容量:128KB;程序存储器类型:FLASH;RAM总容量:20KB;GPIO端口数量:37;")
      (fields (field (name "Manufacturer") "ST(意法半导体)"))
      (libsource (lib "easyedapro") (part "STM32F103CBT6"))
    )
    (comp (ref "U2")
      (value "RC6621A")
      (footprint "easyedapro:BULETM-SMD_18P-L15.2-W11.2-P1.27")
      (description "从机、主从一体透传协议")
      (fields (field (name "Manufacturer") "RF Crazy(智汉)"))
      (libsource (lib "easyedapro") (part "RC6621A"))
    )
    (comp (ref "X1")
      (value "8MHz")
      (footprint "easyedapro:CRYSTAL-SMD_L5.0-W3.2")
      (description "频率:8MHz;频率公差:±10ppm;负载电容:20pF;")
      (fields (field (name "Manufacturer Part") "X50328MSB2GI") (field (name "Manufacturer") "YXC(扬兴晶振)"))
      (libsource (lib "easyedapro") (part "X50328MSB2GI"))
    )
  )
  (nets
    (net (code "1") (name "3V3") (class "Default")
      (node (ref "C1") (pin "1") (pinfunction "1_1") (pintype "input"))
      (node (ref "C15") (pin "1") (pinfunction "1_1") (pintype "input"))
      (node (ref "C16") (pin "1") (pinfunction "1_1") (pintype "input"))
      (node (ref "C17") (pin "1") (pinfunction "1_1") (pintype "input"))
      (node (ref "C18") (pin "1") (pinfunction "1_1") (pintype "input"))
      (node (ref "C2") (pin "2") (pinfunction "2_2") (pintype "input"))
      (node (ref "C24") (pin "2") (pinfunction "2_2") (pintype "input"))
      (node (ref "C29") (pin "2") (pinfunction "2_2") (pintype "input"))
      (node (ref "C8") (pin "2") (pinfunction "2_2") (pintype "input"))
      (node (ref "C9") (pin "2") (pinfunction "2_2") (pintype "input"))
      (node (ref "FPC2") (pin "16") (pinfunction "16_16") (pintype "input"))
      (node (ref "FPC2") (pin "29") (pinfunction "29_29") (pintype "input"))
      (node (ref "H1") (pin "4") (pinfunction "4_4") (pintype "input"))
      (node (ref "R1") (pin "1") (pinfunction "1_1") (pintype "input"))
      (node (ref "R14") (pin "2") (pinfunction "2_2") (pintype "input"))
      (node (ref "R15") (pin "1") (pinfunction "1_1") (pintype "input"))
      (node (ref "R2") (pin "2") (pinfunction "2_2") (pintype "input"))
      (node (ref "R21") (pin "1") (pinfunction "1_1") (pintype "input"))
      (node (ref "R3") (pin "2") (pinfunction "2_2") (pintype "input"))
      (node (ref "R4") (pin "1") (pinfunction "1_1") (pintype "input"))
      (node (ref "U1") (pin "1") (pinfunction "VBAT_1") (pintype "input"))
      (node (ref "U1") (pin "24") (pinfunction "VDD_1_24") (pintype "input"))
      (node (ref "U1") (pin "36") (pinfunction "VDD_2_36") (pintype "input"))
      (node (ref "U1") (pin "48") (pinfunction "VDD_3_48") (pintype "input"))
      (node (ref "U1") (pin "9") (pinfunction "VDD_A_9") (pintype "input"))
      (node (ref "U2") (pin "2") (pinfunction "VCC_2") (pintype "input"))
      (node (ref "U6") (pin "5") (pinfunction "VOUT_5") (pintype "input"))
      (node (ref "U8") (pin "5") (pinfunction "VCC_5") (pintype "input"))
      (node (ref "U8") (pin "8") (pinfunction "V3_8") (pintype "input"))
      (node (ref "U9") (pin "8") (pinfunction "VCC_8") (pintype "input"))
    )
    (net (code "2") (name "BLE_RX") (class "Default")
      (node (ref "U1") (pin "12") (pinfunction "PA2USART2_TXADC12_IN2TIM2_CH3_12") (pintype "input"))
      (node (ref "U2") (pin "17") (pinfunction "GPIO25_17") (pintype "input"))
    )
    (net (code "3") (name "BLE_TX") (class "Default")
      (node (ref "U1") (pin "13") (pinfunction "PA3USART2_RXADC12_IN3TIM2_CH4_13") (pintype "input"))
      (node (ref "U2") (pin "16") (pinfunction "GPIO24_16") (pintype "input"))
    )
    (net (code "4") (name "BOOT0") (class "Default")
      (node (ref "R6") (pin "1") (pinfunction "1_1") (pintype "input"))
      (node (ref "U1") (pin "44") (pinfunction "BOOT0_44") (pintype "input"))
    )
    (net (code "5") (name "BOOT1") (class "Default")
      (node (ref "R9") (pin "1") (pinfunction "1_1") (pintype "input"))
      (node (ref "U1") (pin "20") (pinfunction "PB2BOOT1_20") (pintype "input"))
    )
    (net (code "6") (name "BTN") (class "Default")
      (node (ref "C27") (pin "2") (pinfunction "2_2") (pintype "input"))
      (node (ref "R21") (pin "2") (pinfunction "2_2") (pintype "input"))
      (node (ref "SW3") (pin "2") (pinfunction "2_2") (pintype "input"))
      (node (ref "U1") (pin "14") (pinfunction "PA4SPI1_NSSUSART2_CKADC12_IN4_14") (pintype "input"))
    )
    (net (code "7") (name "CH340_RX") (class "Default")
      (node (ref "U1") (pin "30") (pinfunction "PA9USART1_TXTIM1_CH2_30") (pintype "input"))
      (node (ref "U8") (pin "7") (pinfunction "RXD_7") (pintype "input"))
    )
    (net (code "8") (name "CH340_TX") (class "Default")
      (node (ref "U1") (pin "31") (pinfunction "PA10USART1_RXTIM1_CH3_31") (pintype "input"))
      (node (ref "U8") (pin "6") (pinfunction "TXD_6") (pintype "input"))
    )
    (net (code "9") (name "CLK") (class "Default")
      (node (ref "FPC2") (pin "22") (pinfunction "22_22") (pintype "input"))
      (node (ref "U1") (pin "15") (pinfunction "PA5SPI1_SCKADC12_IN5_15") (pintype "input"))
    )
    (net (code "10") (name "DI") (class "Default")
      (node (ref "FPC2") (pin "23") (pinfunction "23_23") (pintype "input"))
      (node (ref "U1") (pin "17") (pinfunction "PA7SPI1_MOSIADC12_IN7TIM3_CH2_17") (pintype "input"))
    )
    (net (code "11") (name "GND") (class "Default")
      (node (ref "C1") (pin "2") (pinfunction "2_2") (pintype "input"))
      (node (ref "C10") (pin "1") (pinfunction "1_1") (pintype "input"))
      (node (ref "C11") (pin "2") (pinfunction "2_2") (pintype "input"))
      (node (ref "C12") (pin "1") (pinfunction "1_1") (pintype "input"))
      (node (ref "C13") (pin "1") (pinfunction "1_1") (pintype "input"))
      (node (ref "C14") (pin "1") (pinfunction "1_1") (pintype "input"))
      (node (ref "C15") (pin "2") (pinfunction "2_2") (pintype "input"))
      (node (ref "C16") (pin "2") (pinfunction "2_2") (pintype "input"))
      (node (ref "C17") (pin "2") (pinfunction "2_2") (pintype "input"))
      (node (ref "C18") (pin "2") (pinfunction "2_2") (pintype "input"))
      (node (ref "C19") (pin "1") (pinfunction "1_1") (pintype "input"))
      (node (ref "C2") (pin "1") (pinfunction "1_1") (pintype "input"))
      (node (ref "C20") (pin "1") (pinfunction "1_1") (pintype "input"))
      (node (ref "C21") (pin "1") (pinfunction "1_1") (pintype "input"))
      (node (ref "C22") (pin "1") (pinfunction "1_1") (pintype "input"))
      (node (ref "C23") (pin "1") (pinfunction "1_1") (pintype "input"))
      (node (ref "C24") (pin "1") (pinfunction "1_1") (pintype "input"))
      (node (ref "C25") (pin "1") (pinfunction "1_1") (pintype "input"))
      (node (ref "C26") (pin "1") (pinfunction "1_1") (pintype "input"))
      (node (ref "C27") (pin "1") (pinfunction "1_1") (pintype "input"))
      (node (ref "C29") (pin "1") (pinfunction "1_1") (pintype "input"))
      (node (ref "C3") (pin "2") (pinfunction "2_2") (pintype "input"))
      (node (ref "C4") (pin "1") (pinfunction "1_1") (pintype "input"))
      (node (ref "C5") (pin "1") (pinfunction "1_1") (pintype "input"))
      (node (ref "C6") (pin "1") (pinfunction "1_1") (pintype "input"))
      (node (ref "C7") (pin "1") (pinfunction "1_1") (pintype "input"))
      (node (ref "C8") (pin "1") (pinfunction "1_1") (pintype "input"))
      (node (ref "C9") (pin "1") (pinfunction "1_1") (pintype "input"))
      (node (ref "FPC1") (pin "1") (pinfunction "1_1") (pintype "input"))
      (node (ref "FPC2") (pin "10") (pinfunction "10_10") (pintype "input"))
      (node (ref "FPC2") (pin "15") (pinfunction "15_15") (pintype "input"))
      (node (ref "FPC2") (pin "20") (pinfunction "20_20") (pintype "input"))
      (node (ref "FPC2") (pin "21") (pinfunction "21_21") (pintype "input"))
      (node (ref "FPC2") (pin "9") (pinfunction "9_9") (pintype "input"))
      (node (ref "H1") (pin "1") (pinfunction "1_1") (pintype "input"))
      (node (ref "LED1") (pin "1") (pinfunction "K_1") (pintype "input"))
      (node (ref "Q3") (pin "2") (pinfunction "S_2") (pintype "input"))
      (node (ref "R10") (pin "1") (pinfunction "1_1") (pintype "input"))
      (node (ref "R12") (pin "1") (pinfunction "1_1") (pintype "input"))
      (node (ref "R13") (pin "1") (pinfunction "1_1") (pintype "input"))
      (node (ref "R16") (pin "1") (pinfunction "1_1") (pintype "input"))
      (node (ref "R17") (pin "2") (pinfunction "2_2") (pintype "input"))
      (node (ref "R18") (pin "1") (pinfunction "1_1") (pintype "input"))
      (node (ref "R22") (pin "1") (pinfunction "1_1") (pintype "input"))
      (node (ref "R23") (pin "2") (pinfunction "2_2") (pintype "input"))
      (node (ref "R5") (pin "1") (pinfunction "1_1") (pintype "input"))
      (node (ref "R6") (pin "2") (pinfunction "2_2") (pintype "input"))
      (node (ref "R9") (pin "2") (pinfunction "2_2") (pintype "input"))
      (node (ref "SW1") (pin "1") (pinfunction "1_1") (pintype "input"))
      (node (ref "SW2") (pin "2") (pinfunction "2_2") (pintype "input"))
      (node (ref "SW3") (pin "1") (pinfunction "1_1") (pintype "input"))
      (node (ref "U1") (pin "23") (pinfunction "VSS_1_23") (pintype "input"))
      (node (ref "U1") (pin "35") (pinfunction "VSS_2_35") (pintype "input"))
      (node (ref "U1") (pin "47") (pinfunction "VSS_3_47") (pintype "input"))
      (node (ref "U1") (pin "8") (pinfunction "VSS_A_8") (pintype "input"))
      (node (ref "U2") (pin "1") (pinfunction "GND_1") (pintype "input"))
      (node (ref "U3") (pin "10") (pinfunction "AGND_10") (pintype "input"))
      (node (ref "U3") (pin "11") (pinfunction "PGND_11") (pintype "input"))
      (node (ref "U3") (pin "14") (pinfunction "AGND_14") (pintype "input"))
      (node (ref "U3") (pin "15") (pinfunction "PGND_15") (pintype "input"))
      (node (ref "U4") (pin "2") (pinfunction "GND_2") (pintype "input"))
      (node (ref "U5") (pin "1") (pinfunction "PGND_1") (pintype "input"))
      (node (ref "U5") (pin "5") (pinfunction "GND_5") (pintype "input"))
      (node (ref "U5") (pin "9") (pinfunction "PAD_9") (pintype "input"))
      (node (ref "U6") (pin "2") (pinfunction "VSS_2") (pintype "input"))
      (node (ref "U8") (pin "3") (pinfunction "GND_3") (pintype "input"))
      (node (ref "U9") (pin "4") (pinfunction "GND_4") (pintype "input"))
      (node (ref "USB1") (pin "1") (pinfunction "GND_1") (pintype "input"))
      (node (ref "USB1") (pin "12") (pinfunction "GND_12") (pintype "input"))
      (node (ref "USB1") (pin "13") (pinfunction "SHELL_13") (pintype "input"))
      (node (ref "USB1") (pin "14") (pinfunction "SHELL_14") (pintype "input"))
    )
    (net (code "12") (name "IN1") (class "Default")
      (node (ref "U1") (pin "46") (pinfunction "PB9TIM4_CH4_46") (pintype "input"))
      (node (ref "U3") (pin "7") (pinfunction "IND_7") (pintype "input"))
    )
    (net (code "13") (name "IN2") (class "Default")
      (node (ref "U1") (pin "45") (pinfunction "PB8TIM4_CH3_45") (pintype "input"))
      (node (ref "U3") (pin "6") (pinfunction "INC_6") (pintype "input"))
    )
    (net (code "14") (name "IN3") (class "Default")
      (node (ref "U1") (pin "43") (pinfunction "PB7I2C1_SDATIM4_CH2_43") (pintype "input"))
      (node (ref "U3") (pin "3") (pinfunction "INB_3") (pintype "input"))
    )
    (net (code "15") (name "IN4") (class "Default")
      (node (ref "U1") (pin "42") (pinfunction "PB6I2C1_SCLTIM4_CH1_42") (pintype "input"))
      (node (ref "U3") (pin "2") (pinfunction "INA_2") (pintype "input"))
    )
    (net (code "16") (name "LAT") (class "Default")
      (node (ref "FPC2") (pin "8") (pinfunction "8_8") (pintype "input"))
      (node (ref "U1") (pin "19") (pinfunction "PB1ADC12_IN9TIM3_CH4_19") (pintype "input"))
    )
    (net (code "17") (name "LED") (class "Default")
      (node (ref "LED3") (pin "1") (pinfunction "K_1") (pintype "input"))
      (node (ref "U1") (pin "18") (pinfunction "PB0ADC12_IN8TIM3_CH3_18") (pintype "input"))
    )
    (net (code "18") (name "M_A+") (class "Default")
      (node (ref "FPC2") (pin "3") (pinfunction "3_3") (pintype "input"))
      (node (ref "U3") (pin "12") (pinfunction "OUTC_12") (pintype "input"))
    )
    (net (code "19") (name "M_A-") (class "Default")
      (node (ref "FPC2") (pin "4") (pinfunction "4_4") (pintype "input"))
      (node (ref "U3") (pin "9") (pinfunction "OUTD_9") (pintype "input"))
    )
    (net (code "20") (name "M_B+") (class "Default")
      (node (ref "FPC2") (pin "1") (pinfunction "1_1") (pintype "input"))
      (node (ref "U3") (pin "16") (pinfunction "OUTA_16") (pintype "input"))
    )
    (net (code "21") (name "M_B-") (class "Default")
      (node (ref "FPC2") (pin "2") (pinfunction "2_2") (pintype "input"))
      (node (ref "U3") (pin "13") (pinfunction "OUTB_13") (pintype "input"))
    )
    (net (code "22") (name "NRST") (class "Default")
      (node (ref "C3") (pin "1") (pinfunction "1_1") (pintype "input"))
      (node (ref "R3") (pin "1") (pinfunction "1_1") (pintype "input"))
      (node (ref "SW1") (pin "2") (pinfunction "2_2") (pintype "input"))
      (node (ref "U1") (pin "7") (pinfunction "NRST_7") (pintype "input"))
    )
    (net (code "23") (name "Net-(FPC2-Pad30)") (class "Default")
      (node (ref "FPC2") (pin "30") (pinfunction "30_30") (pintype "input"))
      (node (ref "R17") (pin "1") (pinfunction "1_1") (pintype "input"))
    )
    (net (code "24") (name "Net-(LED1-A)") (class "Default")
      (node (ref "LED1") (pin "2") (pinfunction "A_2") (pintype "input"))
      (node (ref "R1") (pin "2") (pinfunction "2_2") (pintype "input"))
    )
    (net (code "25") (name "Net-(LED2-A)") (class "Default")
      (node (ref "LED2") (pin "1") (pinfunction "A_1") (pintype "input"))
      (node (ref "R7") (pin "2") (pinfunction "2_2") (pintype "input"))
    )
    (net (code "26") (name "Net-(LED2-K)") (class "Default")
      (node (ref "LED2") (pin "2") (pinfunction "K_2") (pintype "input"))
      (node (ref "U4") (pin "1") (pinfunction "CHRG_1") (pintype "input"))
    )
    (net (code "27") (name "Net-(LED3-A)") (class "Default")
      (node (ref "LED3") (pin "2") (pinfunction "A_2") (pintype "input"))
      (node (ref "R4") (pin "2") (pinfunction "2_2") (pintype "input"))
    )
    (net (code "28") (name "Net-(Q1-G)") (class "Default")
      (node (ref "Q1") (pin "4") (pinfunction "G_4") (pintype "input"))
      (node (ref "R20") (pin "1") (pinfunction "1_1") (pintype "input"))
      (node (ref "SW2") (pin "1") (pinfunction "1_1") (pintype "input"))
    )
    (net (code "29") (name "Net-(Q2-G)") (class "Default")
      (node (ref "Q2") (pin "4") (pinfunction "G_4") (pintype "input"))
      (node (ref "Q3") (pin "3") (pinfunction "D_3") (pintype "input"))
      (node (ref "R19") (pin "1") (pinfunction "1_1") (pintype "input"))
    )
    (net (code "30") (name "Net-(U4-PROG)") (class "Default")
      (node (ref "R5") (pin "2") (pinfunction "2_2") (pintype "input"))
      (node (ref "U4") (pin "5") (pinfunction "PROG_5") (pintype "input"))
    )
    (net (code "31") (name "Net-(U5-FB)") (class "Default")
      (node (ref "R11") (pin "1") (pinfunction "1_1") (pintype "input"))
      (node (ref "R12") (pin "2") (pinfunction "2_2") (pintype "input"))
      (node (ref "U5") (pin "6") (pinfunction "FB_6") (pintype "input"))
    )
    (net (code "32") (name "Net-(U5-LX)") (class "Default")
      (node (ref "D1") (pin "2") (pinfunction "2_2") (pintype "input"))
      (node (ref "L1") (pin "2") (pinfunction "2_2") (pintype "input"))
      (node (ref "U5") (pin "8") (pinfunction "LX_8") (pintype "input"))
    )
    (net (code "33") (name "Net-(U5-OC)") (class "Default")
      (node (ref "R13") (pin "2") (pinfunction "2_2") (pintype "input"))
      (node (ref "U5") (pin "2") (pinfunction "OC_2") (pintype "input"))
    )
    (net (code "34") (name "Net-(U9A-INA+)") (class "Default")
      (node (ref "R14") (pin "1") (pinfunction "1_1") (pintype "input"))
      (node (ref "R18") (pin "2") (pinfunction "2_2") (pintype "input"))
      (node (ref "U9") (pin "3") (pinfunction "INA+_3") (pintype "input"))
    )
    (net (code "35") (name "Net-(USB1-CC1)") (class "Default")
      (node (ref "R22") (pin "2") (pinfunction "2_2") (pintype "input"))
      (node (ref "USB1") (pin "4") (pinfunction "CC1_4") (pintype "input"))
    )
    (net (code "36") (name "Net-(USB1-CC2)") (class "Default")
      (node (ref "R23") (pin "1") (pinfunction "1_1") (pintype "input"))
      (node (ref "USB1") (pin "10") (pinfunction "CC2_10") (pintype "input"))
    )
    (net (code "37") (name "OSC_IN") (class "Default")
      (node (ref "C25") (pin "2") (pinfunction "2_2") (pintype "input"))
      (node (ref "U1") (pin "5") (pinfunction "PD0-OSC_IN_5") (pintype "input"))
      (node (ref "X1") (pin "2") (pinfunction "OSC2_2") (pintype "input"))
    )
    (net (code "38") (name "OSC_OUT") (class "Default")
      (node (ref "C26") (pin "2") (pinfunction "2_2") (pintype "input"))
      (node (ref "U1") (pin "6") (pinfunction "PD1-OSC_OUT_6") (pintype "input"))
      (node (ref "X1") (pin "1") (pinfunction "OSC1_1") (pintype "input"))
    )
    (net (code "39") (name "PHE") (class "Default")
      (node (ref "FPC2") (pin "28") (pinfunction "28_28") (pintype "input"))
      (node (ref "R16") (pin "2") (pinfunction "2_2") (pintype "input"))
      (node (ref "U9") (pin "2") (pinfunction "INA-_2") (pintype "input"))
    )
    (net (code "40") (name "PHINT") (class "Default")
      (node (ref "R15") (pin "2") (pinfunction "2_2") (pintype "input"))
      (node (ref "U1") (pin "29") (pinfunction "PA8USART1_CKTIM1_CH1MCO_29") (pintype "input"))
      (node (ref "U9") (pin "1") (pinfunction "OUTA_1") (pintype "output"))
    )
    (net (code "41") (name "POWER_ADC") (class "Default")
      (node (ref "C14") (pin "2") (pinfunction "2_2") (pintype "input"))
      (node (ref "R10") (pin "2") (pinfunction "2_2") (pintype "input"))
      (node (ref "R8") (pin "1") (pinfunction "1_1") (pintype "input"))
      (node (ref "U1") (pin "10") (pinfunction "PA0_WKUPUSART2_CTSADC12_IN0TIM2_CH1_ETR_10") (pintype "input"))
    )
    (net (code "42") (name "STB1") (class "Default")
      (node (ref "FPC2") (pin "11") (pinfunction "11_11") (pintype "input"))
      (node (ref "U1") (pin "21") (pinfunction "PB10I2C2_SCLUSART3_TX_21") (pintype "input"))
    )
    (net (code "43") (name "STB2") (class "Default")
      (node (ref "FPC2") (pin "12") (pinfunction "12_12") (pintype "input"))
      (node (ref "U1") (pin "22") (pinfunction "PB11I2C2_SDAUSART3_RX-_22") (pintype "input"))
    )
    (net (code "44") (name "STB3") (class "Default")
      (node (ref "FPC2") (pin "13") (pinfunction "13_13") (pintype "input"))
      (node (ref "U1") (pin "25") (pinfunction "PB12SPI2_NSSI2C2_SMBAUSART3_CKTIM1_BKIN_25") (pintype "input"))
    )
    (net (code "45") (name "STB4") (class "Default")
      (node (ref "FPC2") (pin "17") (pinfunction "17_17") (pintype "input"))
      (node (ref "U1") (pin "26") (pinfunction "PB13SPI2_SCKUSART3_CTSTIM1_CH1N_26") (pintype "input"))
    )
    (net (code "46") (name "STB5") (class "Default")
      (node (ref "FPC2") (pin "18") (pinfunction "18_18") (pintype "input"))
      (node (ref "U1") (pin "27") (pinfunction "PB14SPI2_MISOUSART3_RTSTIM1_CH2N_27") (pintype "input"))
    )
    (net (code "47") (name "STB6") (class "Default")
      (node (ref "FPC2") (pin "19") (pinfunction "19_19") (pintype "input"))
      (node (ref "U1") (pin "28") (pinfunction "PB15SPI2_MOSITIM1_CH3N_28") (pintype "input"))
    )
    (net (code "48") (name "SWCLK") (class "Default")
      (node (ref "H1") (pin "3") (pinfunction "3_3") (pintype "input"))
      (node (ref "U1") (pin "37") (pinfunction "PA14JTCKSWCLK_37") (pintype "input"))
    )
    (net (code "49") (name "SWDIO") (class "Default")
      (node (ref "H1") (pin "2") (pinfunction "2_2") (pintype "input"))
      (node (ref "U1") (pin "34") (pinfunction "PA13JTMSSWDIO_34") (pintype "input"))
    )
    (net (code "50") (name "THER") (class "Default")
      (node (ref "FPC2") (pin "14") (pinfunction "14_14") (pintype "input"))
      (node (ref "R2") (pin "1") (pinfunction "1_1") (pintype "input"))
      (node (ref "U1") (pin "11") (pinfunction "PA1USART2_RTSADC12_IN1TIM2_CH2_11") (pintype "input"))
    )
    (net (code "51") (name "UD+") (class "Default")
      (node (ref "U8") (pin "1") (pinfunction "UD+_1") (pintype "input"))
      (node (ref "USB1") (pin "6") (pinfunction "DP1_6") (pintype "input"))
      (node (ref "USB1") (pin "8") (pinfunction "DP2_8") (pintype "input"))
    )
    (net (code "52") (name "UD-") (class "Default")
      (node (ref "U8") (pin "2") (pinfunction "UD-_2") (pintype "input"))
      (node (ref "USB1") (pin "5") (pinfunction "DN2_5") (pintype "input"))
      (node (ref "USB1") (pin "7") (pinfunction "DN1_7") (pintype "input"))
    )
    (net (code "53") (name "VBAT") (class "Default")
      (node (ref "C12") (pin "2") (pinfunction "2_2") (pintype "input"))
      (node (ref "C13") (pin "2") (pinfunction "2_2") (pintype "input"))
      (node (ref "FPC1") (pin "2") (pinfunction "2_2") (pintype "input"))
      (node (ref "Q1") (pin "1") (pinfunction "S_1") (pintype "input"))
      (node (ref "Q1") (pin "2") (pinfunction "S_2") (pintype "input"))
      (node (ref "Q1") (pin "3") (pinfunction "S_3") (pintype "input"))
      (node (ref "R20") (pin "2") (pinfunction "2_2") (pintype "input"))
      (node (ref "U4") (pin "3") (pinfunction "BAT_3") (pintype "input"))
    )
    (net (code "54") (name "VBAT_OUT") (class "Default")
      (node (ref "C23") (pin "2") (pinfunction "2_2") (pintype "input"))
      (node (ref "C4") (pin "2") (pinfunction "2_2") (pintype "input"))
      (node (ref "C5") (pin "2") (pinfunction "2_2") (pintype "input"))
      (node (ref "Q1") (pin "5") (pinfunction "D_5") (pintype "input"))
      (node (ref "Q1") (pin "6") (pinfunction "D_6") (pintype "input"))
      (node (ref "Q1") (pin "7") (pinfunction "D_7") (pintype "input"))
      (node (ref "Q1") (pin "8") (pinfunction "D_8") (pintype "input"))
      (node (ref "Q2") (pin "1") (pinfunction "S_1") (pintype "input"))
      (node (ref "Q2") (pin "2") (pinfunction "S_2") (pintype "input"))
      (node (ref "Q2") (pin "3") (pinfunction "S_3") (pintype "input"))
      (node (ref "R19") (pin "2") (pinfunction "2_2") (pintype "input"))
      (node (ref "R8") (pin "2") (pinfunction "2_2") (pintype "input"))
      (node (ref "U3") (pin "4") (pinfunction "VDD_4") (pintype "input"))
      (node (ref "U3") (pin "8") (pinfunction "VDD_8") (pintype "input"))
      (node (ref "U6") (pin "1") (pinfunction "VIN_1") (pintype "input"))
      (node (ref "U6") (pin "3") (pinfunction "CE_3") (pintype "input"))
    )
    (net (code "55") (name "VBUS") (class "Default")
      (node (ref "C10") (pin "2") (pinfunction "2_2") (pintype "input"))
      (node (ref "C11") (pin "1") (pinfunction "1_1") (pintype "input"))
      (node (ref "R7") (pin "1") (pinfunction "1_1") (pintype "input"))
      (node (ref "U4") (pin "4") (pinfunction "VCC_4") (pintype "input"))
      (node (ref "USB1") (pin "11") (pinfunction "VBUS_11") (pintype "input"))
      (node (ref "USB1") (pin "2") (pinfunction "VBUS_2") (pintype "input"))
    )
    (net (code "56") (name "VCC_IN") (class "Default")
      (node (ref "C19") (pin "2") (pinfunction "2_2") (pintype "input"))
      (node (ref "C20") (pin "2") (pinfunction "2_2") (pintype "input"))
      (node (ref "L1") (pin "1") (pinfunction "1_1") (pintype "input"))
      (node (ref "Q2") (pin "5") (pinfunction "D_5") (pintype "input"))
      (node (ref "Q2") (pin "6") (pinfunction "D_6") (pintype "input"))
      (node (ref "Q2") (pin "7") (pinfunction "D_7") (pintype "input"))
      (node (ref "Q2") (pin "8") (pinfunction "D_8") (pintype "input"))
      (node (ref "U5") (pin "3") (pinfunction "VIN_3") (pintype "input"))
      (node (ref "U5") (pin "4") (pinfunction "EN_4") (pintype "input"))
    )
    (net (code "57") (name "VH") (class "Default")
      (node (ref "C21") (pin "2") (pinfunction "2_2") (pintype "input"))
      (node (ref "C22") (pin "2") (pinfunction "2_2") (pintype "input"))
      (node (ref "C6") (pin "2") (pinfunction "2_2") (pintype "input"))
      (node (ref "C7") (pin "2") (pinfunction "2_2") (pintype "input"))
      (node (ref "D1") (pin "1") (pinfunction "1_1") (pintype "input"))
      (node (ref "FPC2") (pin "24") (pinfunction "24_24") (pintype "input"))
      (node (ref "FPC2") (pin "25") (pinfunction "25_25") (pintype "input"))
      (node (ref "FPC2") (pin "5") (pinfunction "5_5") (pintype "input"))
      (node (ref "FPC2") (pin "6") (pinfunction "6_6") (pintype "input"))
      (node (ref "R11") (pin "2") (pinfunction "2_2") (pintype "input"))
    )
    (net (code "58") (name "VH_EN") (class "Default")
      (node (ref "Q3") (pin "1") (pinfunction "G_1") (pintype "input"))
      (node (ref "U1") (pin "32") (pinfunction "PA11USART1_CTSCAN_RXTIM1_CH4USBDM_32") (pintype "input"))
    )
    (net (code "59") (name "unconnected-(FPC1-Pad3)") (class "Default")
      (node (ref "FPC1") (pin "3") (pinfunction "3_3") (pintype "input+no_connect"))
    )
    (net (code "60") (name "unconnected-(FPC1-Pad4)") (class "Default")
      (node (ref "FPC1") (pin "4") (pinfunction "4_4") (pintype "input+no_connect"))
    )
    (net (code "61") (name "unconnected-(FPC2-Pad7)") (class "Default")
      (node (ref "FPC2") (pin "7") (pinfunction "7_7") (pintype "input+no_connect"))
    )
    (net (code "62") (name "unconnected-(FPC2-Pad26)") (class "Default")
      (node (ref "FPC2") (pin "26") (pinfunction "26_26") (pintype "input+no_connect"))
    )
    (net (code "63") (name "unconnected-(FPC2-Pad27)") (class "Default")
      (node (ref "FPC2") (pin "27") (pinfunction "27_27") (pintype "input+no_connect"))
    )
    (net (code "64") (name "unconnected-(FPC2-Pad31)") (class "Default")
      (node (ref "FPC2") (pin "31") (pinfunction "31_31") (pintype "input+no_connect"))
    )
    (net (code "65") (name "unconnected-(FPC2-Pad32)") (class "Default")
      (node (ref "FPC2") (pin "32") (pinfunction "32_32") (pintype "input+no_connect"))
    )
    (net (code "66") (name "unconnected-(SW2-Pad3)") (class "Default")
      (node (ref "SW2") (pin "3") (pinfunction "3_3") (pintype "input+no_connect"))
    )
    (net (code "67") (name "unconnected-(SW3-EP-Pad3)") (class "Default")
      (node (ref "SW3") (pin "3") (pinfunction "EP_3") (pintype "input+no_connect"))
    )
    (net (code "68") (name "unconnected-(U1-PA6SPI1_MISOADC12_IN6TIM3_CH1-Pad16)") (class "Default")
      (node (ref "U1") (pin "16") (pinfunction "PA6SPI1_MISOADC12_IN6TIM3_CH1_16") (pintype "input+no_connect"))
    )
    (net (code "69") (name "unconnected-(U1-PA12USART1_RTSCAN_TXTIM1_ETRUSBDP-Pad33)") (class "Default")
      (node (ref "U1") (pin "33") (pinfunction "PA12USART1_RTSCAN_TXTIM1_ETRUSBDP_33") (pintype "input+no_connect"))
    )
    (net (code "70") (name "unconnected-(U1-PA15JTDI-Pad38)") (class "Default")
      (node (ref "U1") (pin "38") (pinfunction "PA15JTDI_38") (pintype "input+no_connect"))
    )
    (net (code "71") (name "unconnected-(U1-PB3JTDO-Pad39)") (class "Default")
      (node (ref "U1") (pin "39") (pinfunction "PB3JTDO_39") (pintype "input+no_connect"))
    )
    (net (code "72") (name "unconnected-(U1-PB4NJTRST-Pad40)") (class "Default")
      (node (ref "U1") (pin "40") (pinfunction "PB4NJTRST_40") (pintype "input+no_connect"))
    )
    (net (code "73") (name "unconnected-(U1-PB5I2C1_SMBA-Pad41)") (class "Default")
      (node (ref "U1") (pin "41") (pinfunction "PB5I2C1_SMBA_41") (pintype "input+no_connect"))
    )
    (net (code "74") (name "unconnected-(U1-PC13-TAMPER-RTC-Pad2)") (class "Default")
      (node (ref "U1") (pin "2") (pinfunction "PC13-TAMPER-RTC_2") (pintype "input+no_connect"))
    )
    (net (code "75") (name "unconnected-(U1-PC14-OSC32_IN-Pad3)") (class "Default")
      (node (ref "U1") (pin "3") (pinfunction "PC14-OSC32_IN_3") (pintype "input+no_connect"))
    )
    (net (code "76") (name "unconnected-(U1-PC15-OSC32_OUT-Pad4)") (class "Default")
      (node (ref "U1") (pin "4") (pinfunction "PC15-OSC32_OUT_4") (pintype "input+no_connect"))
    )
    (net (code "77") (name "unconnected-(U2-GPIO00{slash}SWC-Pad3)") (class "Default")
      (node (ref "U2") (pin "3") (pinfunction "GPIO00/SWC_3") (pintype "input+no_connect"))
    )
    (net (code "78") (name "unconnected-(U2-GPIO01{slash}SWD-Pad4)") (class "Default")
      (node (ref "U2") (pin "4") (pinfunction "GPIO01/SWD_4") (pintype "input+no_connect"))
    )
    (net (code "79") (name "unconnected-(U2-GPIO04-Pad7)") (class "Default")
      (node (ref "U2") (pin "7") (pinfunction "GPIO04_7") (pintype "input+no_connect"))
    )
    (net (code "80") (name "unconnected-(U2-GPIO05-Pad8)") (class "Default")
      (node (ref "U2") (pin "8") (pinfunction "GPIO05_8") (pintype "input+no_connect"))
    )
    (net (code "81") (name "unconnected-(U2-GPIO06-Pad9)") (class "Default")
      (node (ref "U2") (pin "9") (pinfunction "GPIO06_9") (pintype "input+no_connect"))
    )
    (net (code "82") (name "unconnected-(U2-GPIO07-Pad6)") (class "Default")
      (node (ref "U2") (pin "6") (pinfunction "GPIO07_6") (pintype "input+no_connect"))
    )
    (net (code "83") (name "unconnected-(U2-GPIO08-Pad18)") (class "Default")
      (node (ref "U2") (pin "18") (pinfunction "GPIO08_18") (pintype "input+no_connect"))
    )
    (net (code "84") (name "unconnected-(U2-GPIO09-Pad10)") (class "Default")
      (node (ref "U2") (pin "10") (pinfunction "GPIO09_10") (pintype "input+no_connect"))
    )
    (net (code "85") (name "unconnected-(U2-GPIO10-Pad11)") (class "Default")
      (node (ref "U2") (pin "11") (pinfunction "GPIO10_11") (pintype "input+no_connect"))
    )
    (net (code "86") (name "unconnected-(U2-GPIO20-Pad12)") (class "Default")
      (node (ref "U2") (pin "12") (pinfunction "GPIO20_12") (pintype "input+no_connect"))
    )
    (net (code "87") (name "unconnected-(U2-GPIO21-Pad13)") (class "Default")
      (node (ref "U2") (pin "13") (pinfunction "GPIO21_13") (pintype "input+no_connect"))
    )
    (net (code "88") (name "unconnected-(U2-GPIO22-Pad14)") (class "Default")
      (node (ref "U2") (pin "14") (pinfunction "GPIO22_14") (pintype "input+no_connect"))
    )
    (net (code "89") (name "unconnected-(U2-GPIO23-Pad15)") (class "Default")
      (node (ref "U2") (pin "15") (pinfunction "GPIO23_15") (pintype "input+no_connect"))
    )
    (net (code "90") (name "unconnected-(U2-RESET-Pad5)") (class "Default")
      (node (ref "U2") (pin "5") (pinfunction "RESET_5") (pintype "input+no_connect"))
    )
    (net (code "91") (name "unconnected-(U3-NC-Pad1)") (class "Default")
      (node (ref "U3") (pin "1") (pinfunction "NC_1") (pintype "input+no_connect"))
    )
    (net (code "92") (name "unconnected-(U3-NC-Pad5)") (class "Default")
      (node (ref "U3") (pin "5") (pinfunction "NC_5") (pintype "input+no_connect"))
    )
    (net (code "93") (name "unconnected-(U5-NC-Pad7)") (class "Default")
      (node (ref "U5") (pin "7") (pinfunction "NC_7") (pintype "input+no_connect"))
    )
    (net (code "94") (name "unconnected-(U6-NC-Pad4)") (class "Default")
      (node (ref "U6") (pin "4") (pinfunction "NC_4") (pintype "input+no_connect"))
    )
    (net (code "95") (name "unconnected-(U8-RTS#-Pad4)") (class "Default")
      (node (ref "U8") (pin "4") (pinfunction "RTS#_4") (pintype "input+no_connect"))
    )
    (net (code "96") (name "unconnected-(USB1-SBU1-Pad9)") (class "Default")
      (node (ref "USB1") (pin "9") (pinfunction "SBU1_9") (pintype "input+no_connect"))
    )
    (net (code "97") (name "unconnected-(USB1-SBU2-Pad3)") (class "Default")
      (node (ref "USB1") (pin "3") (pinfunction "SBU2_3") (pintype "input+no_connect"))
    )
  )
)
